# matrix_8x8_ws2812_LEDs.net
KiCad netlist of a schematic drawn in Altium Designer
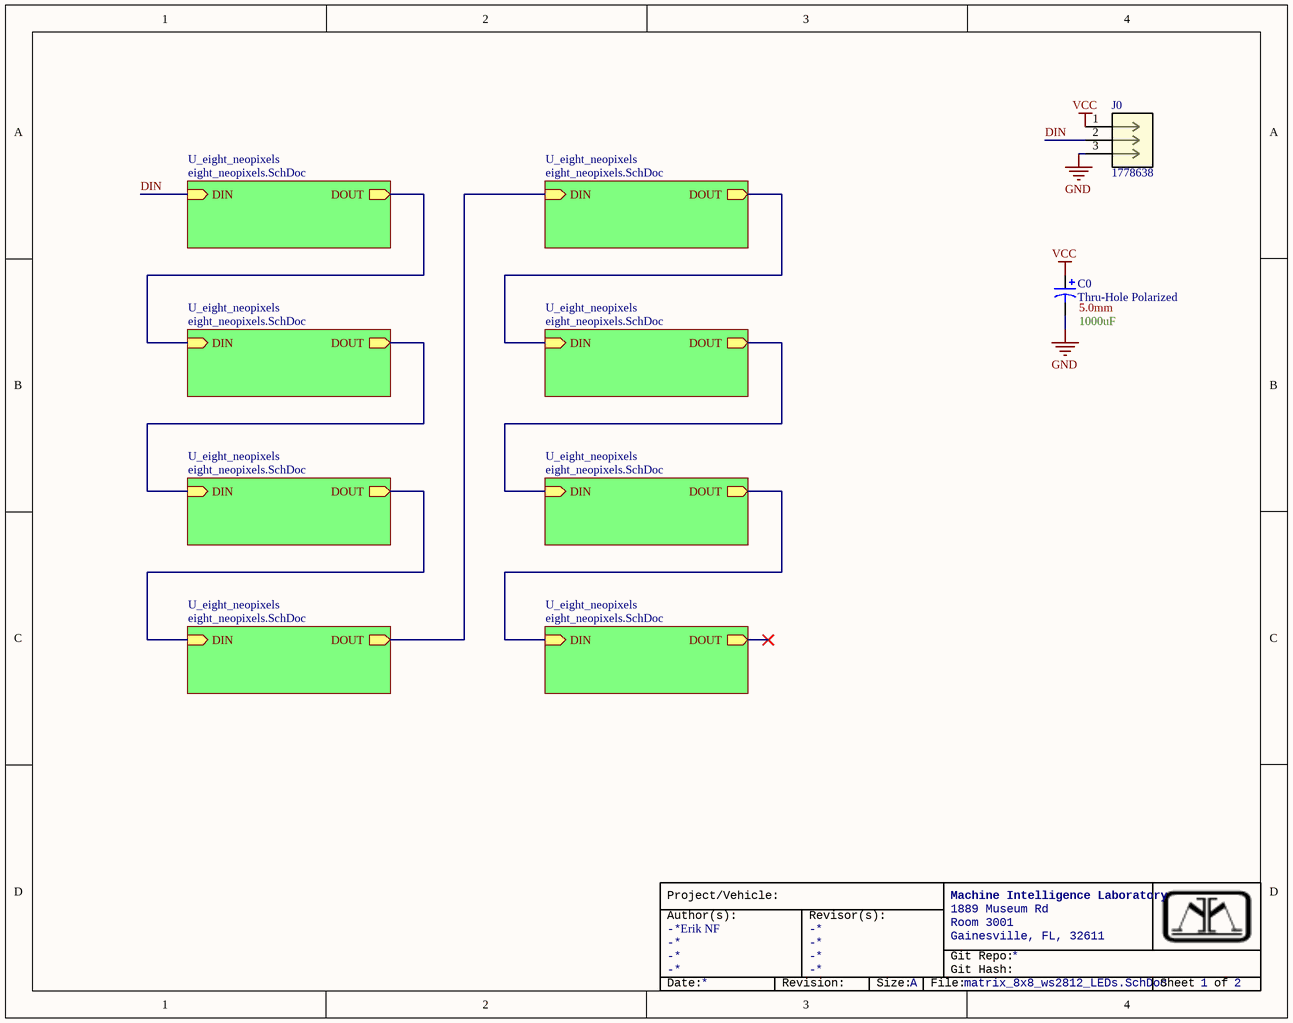
[diagram p0: matrix_8x8_ws2812_LEDs.SchDoc]

(export (version "E")
  (design (tool "Eeschema 10.0.6"))
  (components
    (comp (ref "C0")
      (value "Thru-Hole Polarized")
      (footprint "[Cap] Thru-Hole Polarized 3.5mm")
      (fields
        (field (name "TOLERANCE") "20%")
        (field (name "VOLTAGE") "10V")
        (field (name "PIN SPACING") "5.0mm")
        (field (name "CAPACITANCE") "1000uF")
      )
      (libsource (lib "RADM Components") (part "[Cap] Thru-Hole Polarized"))
    )
    (comp (ref "J0")
      (value "1778638")
      (footprint "CONN_1814854")
      (fields (field (name "COPYRIGHT") "Copyright (C) 2025 Ultra Librarian. All rights reserved."))
      (libsource (lib "1778638") (part "1778638"))
    )
  )
  (nets
    (net (code "1") (name "/DIN") (class "Default")
      (node (ref "J0") (pin "2") (pinfunction "2_2") (pintype "passive"))
    )
    (net (code "10") (name "GND") (class "Default")
      (node (ref "C0") (pin "2") (pinfunction "2_2") (pintype "passive"))
      (node (ref "J0") (pin "3") (pinfunction "3_3") (pintype "passive"))
    )
    (net (code "11") (name "VCC") (class "Default")
      (node (ref "C0") (pin "1") (pinfunction "1_1") (pintype "passive"))
      (node (ref "J0") (pin "1") (pinfunction "1_1") (pintype "passive"))
    )
  )
)
